# GaragentorSteuerung.net
KiCad netlist of a schematic drawn in EAGLE
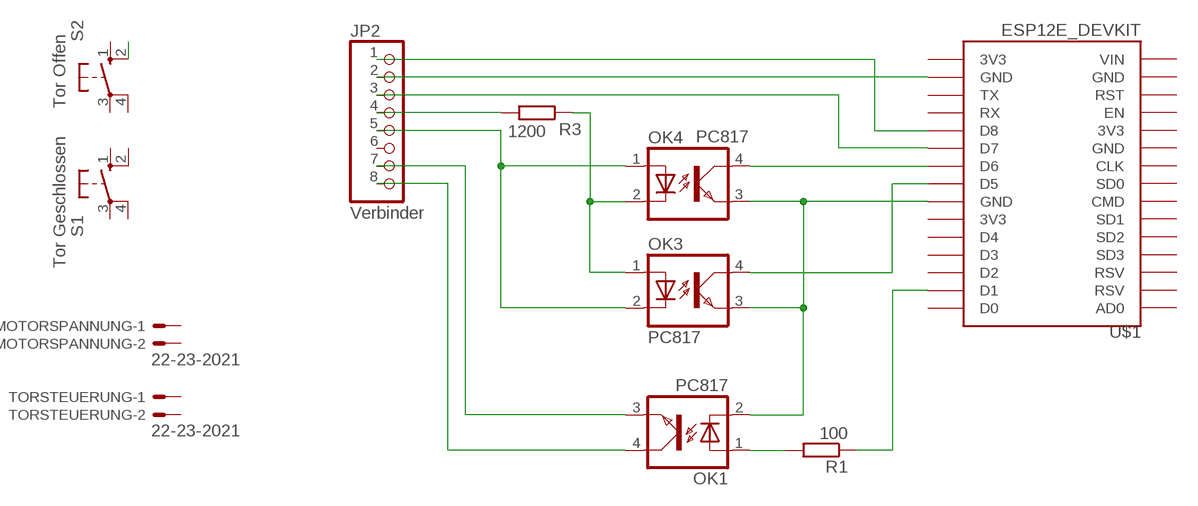
[diagram p0: schematic, sheet 1]

(export (version "E")
  (design (tool "Eeschema 10.0.6"))
  (components
    (comp (ref "JP2")
      (value "Verbinder")
      (footprint "eagle-import:1X08")
      (libsource (lib "eagle-import") (part "PINHD-1X8"))
    )
    (comp (ref "MOTORSPANNUNG")
      (value "22-23-2021")
      (footprint "eagle-import:22-23-2021")
      (fields (field (name "MF") "MOLEX"))
      (libsource (lib "eagle-import") (part "22-23-2021"))
    )
    (comp (ref "OK1")
      (value "PC817")
      (footprint "eagle-import:DIL04")
      (fields (field (name "MPN") "PC817X4J000F"))
      (libsource (lib "eagle-import") (part "PC817"))
    )
    (comp (ref "OK3")
      (value "PC817")
      (footprint "eagle-import:DIL04")
      (fields (field (name "MPN") "PC817X4J000F"))
      (libsource (lib "eagle-import") (part "PC817"))
    )
    (comp (ref "OK4")
      (value "PC817")
      (footprint "eagle-import:DIL04")
      (fields (field (name "MPN") "PC817X4J000F"))
      (libsource (lib "eagle-import") (part "PC817"))
    )
    (comp (ref "R1")
      (value "100")
      (footprint "eagle-import:0207_7")
      (libsource (lib "eagle-import") (part "R-EU_0207/7"))
    )
    (comp (ref "R3")
      (value "1200")
      (footprint "eagle-import:0207_7")
      (libsource (lib "eagle-import") (part "R-EU_0207/7"))
    )
    (comp (ref "S1")
      (value "Tor Geschlossen")
      (footprint "eagle-import:B3F-10XX")
      (fields (field (name "MPN") "B3F-1000"))
      (libsource (lib "eagle-import") (part "10-XX"))
    )
    (comp (ref "S2")
      (value "Tor Offen")
      (footprint "eagle-import:B3F-10XX")
      (fields (field (name "MPN") "B3F-1000"))
      (libsource (lib "eagle-import") (part "10-XX"))
    )
    (comp (ref "TORSTEUERUNG")
      (value "22-23-2021")
      (footprint "eagle-import:22-23-2021")
      (fields (field (name "MF") "MOLEX"))
      (libsource (lib "eagle-import") (part "22-23-2021"))
    )
    (comp (ref "U$1")
      (value "ESP12E_DEVKIT")
      (footprint "eagle-import:ESP12E_DEVKIT")
      (libsource (lib "eagle-import") (part "ESP12E_DEVKIT"))
    )
  )
  (nets
    (net (code "1") (name "Net-(JP2-Pad1)") (class "Default")
      (node (ref "JP2") (pin "1") (pinfunction "1_1") (pintype "passive"))
      (node (ref "U$1") (pin "D8") (pinfunction "D8_D8") (pintype "bidirectional"))
    )
    (net (code "2") (name "Net-(JP2-Pad2)") (class "Default")
      (node (ref "JP2") (pin "2") (pinfunction "2_2") (pintype "passive"))
      (node (ref "U$1") (pin "GND@3") (pinfunction "GND_GND@3") (pintype "bidirectional"))
    )
    (net (code "3") (name "Net-(JP2-Pad3)") (class "Default")
      (node (ref "JP2") (pin "3") (pinfunction "3_3") (pintype "passive"))
      (node (ref "U$1") (pin "D7") (pinfunction "D7_D7") (pintype "bidirectional"))
    )
    (net (code "4") (name "Net-(JP2-Pad4)") (class "Default")
      (node (ref "JP2") (pin "4") (pinfunction "4_4") (pintype "passive"))
      (node (ref "R3") (pin "2") (pinfunction "2_2") (pintype "passive"))
    )
    (net (code "5") (name "Net-(OK1-A)") (class "Default")
      (node (ref "OK1") (pin "1") (pinfunction "A_1") (pintype "passive"))
      (node (ref "R1") (pin "2") (pinfunction "2_2") (pintype "passive"))
    )
    (net (code "6") (name "Net-(OK1-C)") (class "Default")
      (node (ref "OK1") (pin "2") (pinfunction "C_2") (pintype "passive"))
      (node (ref "OK3") (pin "3") (pinfunction "EMIT_3") (pintype "passive"))
      (node (ref "OK4") (pin "3") (pinfunction "EMIT_3") (pintype "passive"))
      (node (ref "U$1") (pin "GND@2") (pinfunction "GND_GND@2") (pintype "bidirectional"))
    )
    (net (code "7") (name "Net-(OK1-COL)") (class "Default")
      (node (ref "JP2") (pin "8") (pinfunction "8_8") (pintype "passive"))
      (node (ref "OK1") (pin "4") (pinfunction "COL_4") (pintype "passive"))
    )
    (net (code "8") (name "Net-(OK1-EMIT)") (class "Default")
      (node (ref "JP2") (pin "7") (pinfunction "7_7") (pintype "passive"))
      (node (ref "OK1") (pin "3") (pinfunction "EMIT_3") (pintype "passive"))
    )
    (net (code "9") (name "Net-(OK3-A)") (class "Default")
      (node (ref "OK3") (pin "1") (pinfunction "A_1") (pintype "passive"))
      (node (ref "OK4") (pin "2") (pinfunction "C_2") (pintype "passive"))
      (node (ref "R3") (pin "1") (pinfunction "1_1") (pintype "passive"))
    )
    (net (code "10") (name "Net-(OK3-C)") (class "Default")
      (node (ref "JP2") (pin "5") (pinfunction "5_5") (pintype "passive"))
      (node (ref "OK3") (pin "2") (pinfunction "C_2") (pintype "passive"))
      (node (ref "OK4") (pin "1") (pinfunction "A_1") (pintype "passive"))
    )
    (net (code "11") (name "Net-(OK3-COL)") (class "Default")
      (node (ref "OK3") (pin "4") (pinfunction "COL_4") (pintype "passive"))
      (node (ref "U$1") (pin "D5") (pinfunction "D5_D5") (pintype "bidirectional"))
    )
    (net (code "12") (name "Net-(OK4-COL)") (class "Default")
      (node (ref "OK4") (pin "4") (pinfunction "COL_4") (pintype "passive"))
      (node (ref "U$1") (pin "D6") (pinfunction "D6_D6") (pintype "bidirectional"))
    )
    (net (code "13") (name "Net-(R1-Pad1)") (class "Default")
      (node (ref "R1") (pin "1") (pinfunction "1_1") (pintype "passive"))
      (node (ref "U$1") (pin "D1") (pinfunction "D1_D1") (pintype "bidirectional"))
    )
    (net (code "14") (name "unconnected-(JP2-Pad6)") (class "Default")
      (node (ref "JP2") (pin "6") (pinfunction "6_6") (pintype "passive"))
    )
    (net (code "15") (name "unconnected-(MOTORSPANNUNGA-S-Pad1)") (class "Default")
      (node (ref "MOTORSPANNUNG") (pin "1") (pinfunction "S_1") (pintype "passive"))
    )
    (net (code "16") (name "unconnected-(MOTORSPANNUNGB-S-Pad2)") (class "Default")
      (node (ref "MOTORSPANNUNG") (pin "2") (pinfunction "S_2") (pintype "passive"))
    )
    (net (code "17") (name "unconnected-(S1-P-Pad3)") (class "Default")
      (node (ref "S1") (pin "3") (pinfunction "P_3") (pintype "passive"))
    )
    (net (code "18") (name "unconnected-(S1-P1-Pad4)") (class "Default")
      (node (ref "S1") (pin "4") (pinfunction "P1_4") (pintype "passive"))
    )
    (net (code "19") (name "unconnected-(S1-S-Pad1)") (class "Default")
      (node (ref "S1") (pin "1") (pinfunction "S_1") (pintype "passive"))
    )
    (net (code "20") (name "unconnected-(S1-S1-Pad2)") (class "Default")
      (node (ref "S1") (pin "2") (pinfunction "S1_2") (pintype "passive"))
    )
    (net (code "21") (name "unconnected-(S2-P-Pad3)") (class "Default")
      (node (ref "S2") (pin "3") (pinfunction "P_3") (pintype "passive"))
    )
    (net (code "22") (name "unconnected-(S2-P1-Pad4)") (class "Default")
      (node (ref "S2") (pin "4") (pinfunction "P1_4") (pintype "passive"))
    )
    (net (code "23") (name "unconnected-(S2-S-Pad1)") (class "Default")
      (node (ref "S2") (pin "1") (pinfunction "S_1") (pintype "passive"))
    )
    (net (code "24") (name "unconnected-(S2-S1-Pad2)") (class "Default")
      (node (ref "S2") (pin "2") (pinfunction "S1_2") (pintype "passive"))
    )
    (net (code "25") (name "unconnected-(TORSTEUERUNGA-S-Pad1)") (class "Default")
      (node (ref "TORSTEUERUNG") (pin "1") (pinfunction "S_1") (pintype "passive"))
    )
    (net (code "26") (name "unconnected-(TORSTEUERUNGB-S-Pad2)") (class "Default")
      (node (ref "TORSTEUERUNG") (pin "2") (pinfunction "S_2") (pintype "passive"))
    )
    (net (code "27") (name "unconnected-(U$1-3V3-Pad3V3@0)") (class "Default")
      (node (ref "U$1") (pin "3V3@0") (pinfunction "3V3_3V3@0") (pintype "bidirectional"))
    )
    (net (code "28") (name "unconnected-(U$1-3V3-Pad3V3@1)") (class "Default")
      (node (ref "U$1") (pin "3V3@1") (pinfunction "3V3_3V3@1") (pintype "bidirectional"))
    )
    (net (code "29") (name "unconnected-(U$1-3V3-Pad3V3@2)") (class "Default")
      (node (ref "U$1") (pin "3V3@2") (pinfunction "3V3_3V3@2") (pintype "bidirectional"))
    )
    (net (code "30") (name "unconnected-(U$1-GND-PadGND@0)") (class "Default")
      (node (ref "U$1") (pin "GND@0") (pinfunction "GND_GND@0") (pintype "bidirectional"))
    )
    (net (code "31") (name "unconnected-(U$1-GND-PadGND@1)") (class "Default")
      (node (ref "U$1") (pin "GND@1") (pinfunction "GND_GND@1") (pintype "bidirectional"))
    )
    (net (code "32") (name "unconnected-(U$1-PadAD0)") (class "Default")
      (node (ref "U$1") (pin "AD0") (pinfunction "AD0_AD0") (pintype "bidirectional"))
    )
    (net (code "33") (name "unconnected-(U$1-PadCLK)") (class "Default")
      (node (ref "U$1") (pin "CLK") (pinfunction "CLK_CLK") (pintype "bidirectional"))
    )
    (net (code "34") (name "unconnected-(U$1-PadCMD)") (class "Default")
      (node (ref "U$1") (pin "CMD") (pinfunction "CMD_CMD") (pintype "bidirectional"))
    )
    (net (code "35") (name "unconnected-(U$1-PadD0)") (class "Default")
      (node (ref "U$1") (pin "D0") (pinfunction "D0_D0") (pintype "bidirectional"))
    )
    (net (code "36") (name "unconnected-(U$1-PadD2)") (class "Default")
      (node (ref "U$1") (pin "D2") (pinfunction "D2_D2") (pintype "bidirectional"))
    )
    (net (code "37") (name "unconnected-(U$1-PadD3)") (class "Default")
      (node (ref "U$1") (pin "D3") (pinfunction "D3_D3") (pintype "bidirectional"))
    )
    (net (code "38") (name "unconnected-(U$1-PadD4)") (class "Default")
      (node (ref "U$1") (pin "D4") (pinfunction "D4_D4") (pintype "bidirectional"))
    )
    (net (code "39") (name "unconnected-(U$1-PadEN)") (class "Default")
      (node (ref "U$1") (pin "EN") (pinfunction "EN_EN") (pintype "bidirectional"))
    )
    (net (code "40") (name "unconnected-(U$1-PadRST)") (class "Default")
      (node (ref "U$1") (pin "RST") (pinfunction "RST_RST") (pintype "bidirectional"))
    )
    (net (code "41") (name "unconnected-(U$1-PadRX)") (class "Default")
      (node (ref "U$1") (pin "RX") (pinfunction "RX_RX") (pintype "bidirectional"))
    )
    (net (code "42") (name "unconnected-(U$1-PadSD0)") (class "Default")
      (node (ref "U$1") (pin "SD0") (pinfunction "SD0_SD0") (pintype "bidirectional"))
    )
    (net (code "43") (name "unconnected-(U$1-PadSD1)") (class "Default")
      (node (ref "U$1") (pin "SD1") (pinfunction "SD1_SD1") (pintype "bidirectional"))
    )
    (net (code "44") (name "unconnected-(U$1-PadSD2)") (class "Default")
      (node (ref "U$1") (pin "SD2") (pinfunction "SD2_SD2") (pintype "bidirectional"))
    )
    (net (code "45") (name "unconnected-(U$1-PadSD3)") (class "Default")
      (node (ref "U$1") (pin "SD3") (pinfunction "SD3_SD3") (pintype "bidirectional"))
    )
    (net (code "46") (name "unconnected-(U$1-PadTX)") (class "Default")
      (node (ref "U$1") (pin "TX") (pinfunction "TX_TX") (pintype "bidirectional"))
    )
    (net (code "47") (name "unconnected-(U$1-PadVIN)") (class "Default")
      (node (ref "U$1") (pin "VIN") (pinfunction "VIN_VIN") (pintype "bidirectional"))
    )
    (net (code "48") (name "unconnected-(U$1-RSV-PadRSV@0)") (class "Default")
      (node (ref "U$1") (pin "RSV@0") (pinfunction "RSV_RSV@0") (pintype "bidirectional"))
    )
    (net (code "49") (name "unconnected-(U$1-RSV-PadRSV@1)") (class "Default")
      (node (ref "U$1") (pin "RSV@1") (pinfunction "RSV_RSV@1") (pintype "bidirectional"))
    )
  )
)
